# PowerLatch.net
KiCad netlist of a schematic drawn in EAGLE
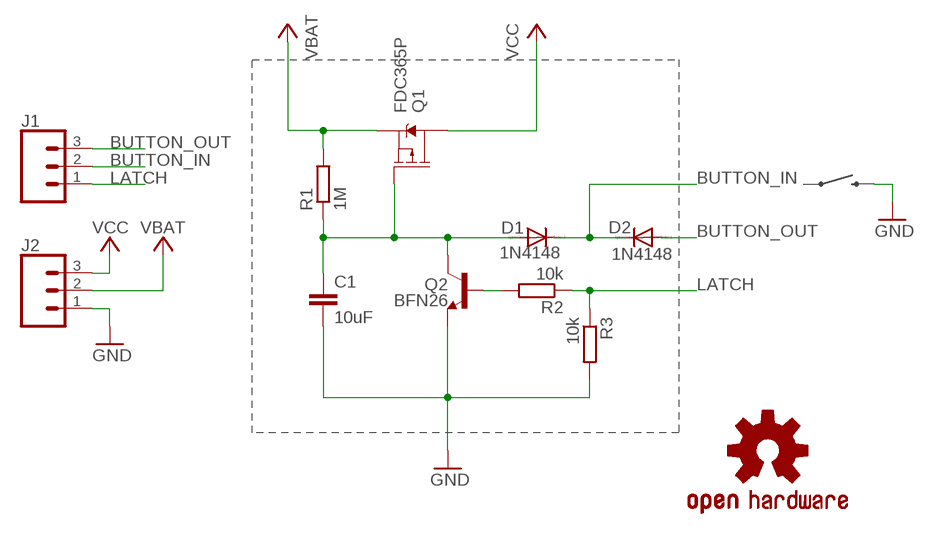
[diagram p0: schematic, sheet 1]

(export (version "E")
  (design (tool "Eeschema 10.0.6"))
  (components
    (comp (ref "C1")
      (value "10uF")
      (footprint "eagle-import:C0603")
      (libsource (lib "eagle-import") (part "C-EUC0603"))
    )
    (comp (ref "D1")
      (value "1N4148")
      (footprint "eagle-import:SOD523")
      (libsource (lib "eagle-import") (part "DIODE-SOD523"))
    )
    (comp (ref "D2")
      (value "1N4148")
      (footprint "eagle-import:SOD523")
      (libsource (lib "eagle-import") (part "DIODE-SOD523"))
    )
    (comp (ref "J1")
      (value "455-1750-1-ND")
      (footprint "eagle-import:1X03")
      (libsource (lib "eagle-import") (part "CONN_03"))
    )
    (comp (ref "J2")
      (value "455-1750-1-ND")
      (footprint "eagle-import:1X03")
      (libsource (lib "eagle-import") (part "CONN_03"))
    )
    (comp (ref "LOGO1")
      (value "OSHW-LOGOS")
      (footprint "eagle-import:OSHW-LOGO-S")
      (libsource (lib "eagle-import") (part "OSHW-LOGOS"))
    )
    (comp (ref "Q1")
      (value "FDC365P")
      (footprint "eagle-import:SSOT6")
      (fields (field (name "SPICEPREFIX") "Q"))
      (libsource (lib "eagle-import") (part "MOSFET_PCH-FDC365P"))
    )
    (comp (ref "Q2")
      (value "BFN26")
      (footprint "eagle-import:SOT23-3")
      (libsource (lib "eagle-import") (part "TRANS_NPN-BFN26"))
    )
    (comp (ref "R1")
      (value "1M")
      (footprint "eagle-import:R0603")
      (libsource (lib "eagle-import") (part "R-EU_R0603"))
    )
    (comp (ref "R2")
      (value "10k")
      (footprint "eagle-import:R0603")
      (libsource (lib "eagle-import") (part "R-EU_R0603"))
    )
    (comp (ref "R3")
      (value "10k")
      (footprint "eagle-import:R0603")
      (libsource (lib "eagle-import") (part "R-EU_R0603"))
    )
  )
  (nets
    (net (code "1") (name "/BUTTON_IN") (class "Default")
      (node (ref "D1") (pin "C") (pinfunction "C_C") (pintype "passive"))
      (node (ref "D2") (pin "C") (pinfunction "C_C") (pintype "passive"))
      (node (ref "J1") (pin "2") (pinfunction "2_2") (pintype "passive"))
    )
    (net (code "2") (name "/BUTTON_OUT") (class "Default")
      (node (ref "D2") (pin "A") (pinfunction "A_A") (pintype "passive"))
      (node (ref "J1") (pin "3") (pinfunction "3_3") (pintype "passive"))
    )
    (net (code "3") (name "/LATCH") (class "Default")
      (node (ref "J1") (pin "1") (pinfunction "1_1") (pintype "passive"))
      (node (ref "R2") (pin "1") (pinfunction "1_1") (pintype "passive"))
      (node (ref "R3") (pin "1") (pinfunction "1_1") (pintype "passive"))
    )
    (net (code "4") (name "GND") (class "Default")
      (node (ref "C1") (pin "2") (pinfunction "2_2") (pintype "passive"))
      (node (ref "J2") (pin "1") (pinfunction "1_1") (pintype "passive"))
      (node (ref "Q2") (pin "2") (pinfunction "E_2") (pintype "passive"))
      (node (ref "R3") (pin "2") (pinfunction "2_2") (pintype "passive"))
    )
    (net (code "5") (name "Net-(Q1-G)") (class "Default")
      (node (ref "C1") (pin "1") (pinfunction "1_1") (pintype "passive"))
      (node (ref "D1") (pin "A") (pinfunction "A_A") (pintype "passive"))
      (node (ref "Q1") (pin "3") (pinfunction "G_3") (pintype "bidirectional"))
      (node (ref "Q2") (pin "3") (pinfunction "C_3") (pintype "passive"))
      (node (ref "R1") (pin "1") (pinfunction "1_1") (pintype "passive"))
    )
    (net (code "6") (name "Net-(Q2-B)") (class "Default")
      (node (ref "Q2") (pin "1") (pinfunction "B_1") (pintype "passive"))
      (node (ref "R2") (pin "2") (pinfunction "2_2") (pintype "passive"))
    )
    (net (code "7") (name "VBAT") (class "Default")
      (node (ref "J2") (pin "2") (pinfunction "2_2") (pintype "passive"))
      (node (ref "Q1") (pin "4") (pinfunction "S_4") (pintype "bidirectional"))
      (node (ref "R1") (pin "2") (pinfunction "2_2") (pintype "passive"))
    )
    (net (code "8") (name "VCC") (class "Default")
      (node (ref "J2") (pin "3") (pinfunction "3_3") (pintype "passive"))
      (node (ref "Q1") (pin "1") (pinfunction "D_1") (pintype "bidirectional"))
      (node (ref "Q1") (pin "2") (pinfunction "D_2") (pintype "bidirectional"))
      (node (ref "Q1") (pin "5") (pinfunction "D_5") (pintype "bidirectional"))
      (node (ref "Q1") (pin "6") (pinfunction "D_6") (pintype "bidirectional"))
    )
  )
)
